# OLED_1_5-inch_Sch.net
KiCad netlist of a schematic drawn in Altium Designer
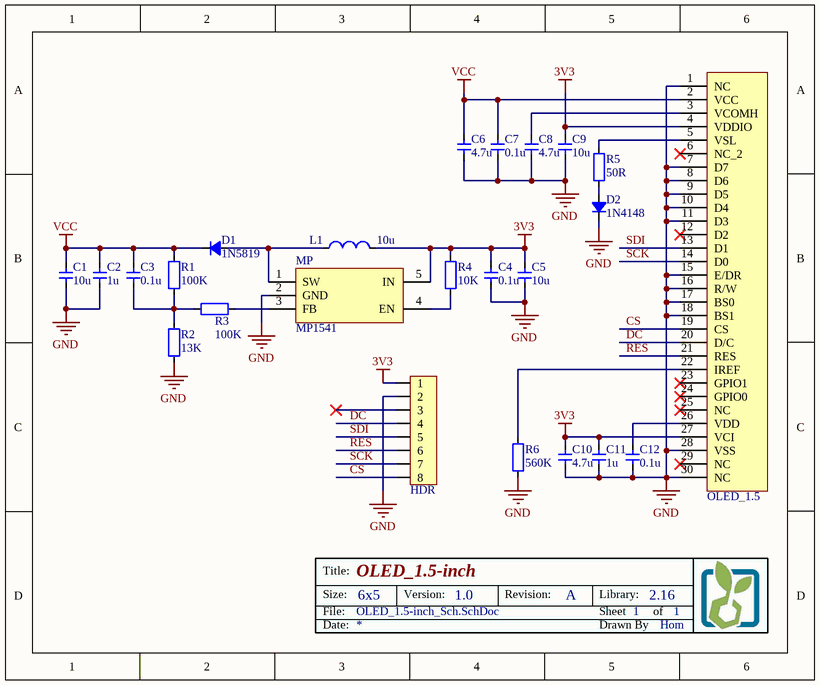
[diagram p0: OLED_1.5-inch_Sch.SchDoc]

(export (version "E")
  (design (tool "Eeschema 10.0.6"))
  (components
    (comp (ref "C1")
      (value "10u")
      (footprint "PCB_PassiveCap:CAP_0805")
      (description "Capacitor")
      (fields (field (name "Comment") "Cap_0805"))
      (libsource (lib "SCH_Passive") (part "Cap_0805"))
    )
    (comp (ref "C2")
      (value "1u")
      (footprint "PCB_PassiveCap:CAP_0805")
      (description "Capacitor")
      (fields (field (name "Comment") "Cap_0805"))
      (libsource (lib "SCH_Passive") (part "Cap_0805"))
    )
    (comp (ref "C3")
      (value "0.1u")
      (footprint "PCB_PassiveCap:CAP_0805")
      (description "Capacitor")
      (fields (field (name "Comment") "Cap_0805"))
      (libsource (lib "SCH_Passive") (part "Cap_0805"))
    )
    (comp (ref "C4")
      (value "0.1u")
      (footprint "PCB_PassiveCap:CAP_0603")
      (description "Capacitor")
      (fields (field (name "Comment") "Cap_0603"))
      (libsource (lib "SCH_Passive") (part "Cap_0603"))
    )
    (comp (ref "C5")
      (value "10u")
      (footprint "PCB_PassiveCap:CAP_0603")
      (description "Capacitor")
      (fields (field (name "Comment") "Cap_0603"))
      (libsource (lib "SCH_Passive") (part "Cap_0603"))
    )
    (comp (ref "C6")
      (value "4.7u")
      (footprint "PCB_PassiveCap:CAP_0805")
      (description "Capacitor")
      (fields (field (name "Comment") "Cap_0805"))
      (libsource (lib "SCH_Passive") (part "Cap_0805"))
    )
    (comp (ref "C7")
      (value "0.1u")
      (footprint "PCB_PassiveCap:CAP_0805")
      (description "Capacitor")
      (fields (field (name "Comment") "Cap_0805"))
      (libsource (lib "SCH_Passive") (part "Cap_0805"))
    )
    (comp (ref "C8")
      (value "4.7u")
      (footprint "PCB_PassiveCap:CAP_0805")
      (description "Capacitor")
      (fields (field (name "Comment") "Cap_0805"))
      (libsource (lib "SCH_Passive") (part "Cap_0805"))
    )
    (comp (ref "C9")
      (value "10u")
      (footprint "PCB_PassiveCap:CAP_0603")
      (description "Capacitor")
      (fields (field (name "Comment") "Cap_0603"))
      (libsource (lib "SCH_Passive") (part "Cap_0603"))
    )
    (comp (ref "C10")
      (value "4.7u")
      (footprint "PCB_PassiveCap:CAP_0603")
      (description "Capacitor")
      (fields (field (name "Comment") "Cap_0603"))
      (libsource (lib "SCH_Passive") (part "Cap_0603"))
    )
    (comp (ref "C11")
      (value "1u")
      (footprint "PCB_PassiveCap:CAP_0603")
      (description "Capacitor")
      (fields (field (name "Comment") "Cap_0603"))
      (libsource (lib "SCH_Passive") (part "Cap_0603"))
    )
    (comp (ref "C12")
      (value "0.1u")
      (footprint "PCB_PassiveCap:CAP_0603")
      (description "Capacitor")
      (fields (field (name "Comment") "Cap_0603"))
      (libsource (lib "SCH_Passive") (part "Cap_0603"))
    )
    (comp (ref "D1")
      (value "1N5819")
      (footprint "PCB_ActiveDIO:SOD-123")
      (description "Diode")
      (libsource (lib "SCH_Active") (part "Diode_SOD123"))
    )
    (comp (ref "D2")
      (value "1N4148")
      (footprint "PCB_ActiveDIO:SOD-323")
      (description "Diode")
      (libsource (lib "SCH_Active") (part "Diode_SOD323"))
    )
    (comp (ref "HDR")
      (value "HDR1x8_2.54")
      (footprint "PCB_ConnectorHDR:HDR1X8_2.54_180")
      (description "Header")
      (libsource (lib "SCH_ConnectorHDR") (part "HDR1x8_2.54"))
    )
    (comp (ref "L1")
      (value "10u")
      (footprint "PCB_PassiveInd:IND_CD32")
      (description "Inductor")
      (fields (field (name "Comment") "Ind_CD32"))
      (libsource (lib "SCH_Passive") (part "Ind_CD32"))
    )
    (comp (ref "MP")
      (value "MP1541")
      (footprint "PCB_IntegratedCircuit:SOT23-5")
      (description "Boost")
      (libsource (lib "SCH_IntegratedCircuit") (part "MP1541"))
    )
    (comp (ref "OLED_1.5")
      (value "OLED_1.5_SSD1351")
      (footprint "PCB_Module:OLED_1.5_128x128_SSD1351")
      (description "OLED")
      (libsource (lib "SCH_Module") (part "OLED_1.5_SSD1351"))
    )
    (comp (ref "R1")
      (value "100K")
      (footprint "PCB_PassiveRes:RES_0603")
      (description "Resistor")
      (fields (field (name "Comment") "Res_0603"))
      (libsource (lib "") (part "Res_0603_2"))
    )
    (comp (ref "R2")
      (value "13K")
      (footprint "PCB_PassiveRes:RES_0603")
      (description "Resistor")
      (fields (field (name "Comment") "Res_0603"))
      (libsource (lib "") (part "Res_0603_2"))
    )
    (comp (ref "R3")
      (value "100K")
      (footprint "PCB_PassiveRes:RES_0603")
      (description "Resistor")
      (fields (field (name "Comment") "Res_0603"))
      (libsource (lib "") (part "Res_0603_1"))
    )
    (comp (ref "R4")
      (value "10K")
      (footprint "PCB_PassiveRes:RES_0603")
      (description "Resistor")
      (fields (field (name "Comment") "Res_0603"))
      (libsource (lib "") (part "Res_0603_2"))
    )
    (comp (ref "R5")
      (value "50R")
      (footprint "PCB_PassiveRes:RES_0603")
      (description "Resistor")
      (fields (field (name "Comment") "Res_0603"))
      (libsource (lib "SCH_Passive") (part "Res_0603"))
    )
    (comp (ref "R6")
      (value "560K")
      (footprint "PCB_PassiveRes:RES_0603")
      (description "Resistor")
      (fields (field (name "Comment") "Res_0603"))
      (libsource (lib "SCH_Passive") (part "Res_0603"))
    )
  )
  (nets
    (net (code "1") (name "/CS") (class "Default")
      (node (ref "HDR") (pin "8") (pinfunction "8_8") (pintype "passive"))
      (node (ref "OLED_1.5") (pin "19") (pinfunction "CS_19") (pintype "passive"))
    )
    (net (code "2") (name "/DC") (class "Default")
      (node (ref "HDR") (pin "4") (pinfunction "4_4") (pintype "passive"))
      (node (ref "OLED_1.5") (pin "20") (pinfunction "D/C_20") (pintype "passive"))
    )
    (net (code "3") (name "/RES") (class "Default")
      (node (ref "HDR") (pin "6") (pinfunction "6_6") (pintype "passive"))
      (node (ref "OLED_1.5") (pin "21") (pinfunction "RES_21") (pintype "passive"))
    )
    (net (code "4") (name "/SCK") (class "Default")
      (node (ref "HDR") (pin "7") (pinfunction "7_7") (pintype "passive"))
      (node (ref "OLED_1.5") (pin "14") (pinfunction "D0_14") (pintype "passive"))
    )
    (net (code "5") (name "/SDI") (class "Default")
      (node (ref "HDR") (pin "5") (pinfunction "5_5") (pintype "passive"))
      (node (ref "OLED_1.5") (pin "13") (pinfunction "D1_13") (pintype "passive"))
    )
    (net (code "6") (name "3V3") (class "Default")
      (node (ref "C10") (pin "2") (pinfunction "2_2") (pintype "passive"))
      (node (ref "C11") (pin "2") (pinfunction "2_2") (pintype "passive"))
      (node (ref "C4") (pin "2") (pinfunction "2_2") (pintype "passive"))
      (node (ref "C5") (pin "2") (pinfunction "2_2") (pintype "passive"))
      (node (ref "C9") (pin "2") (pinfunction "2_2") (pintype "passive"))
      (node (ref "HDR") (pin "1") (pinfunction "1_1") (pintype "passive"))
      (node (ref "L1") (pin "2") (pinfunction "2_2") (pintype "passive"))
      (node (ref "MP") (pin "5") (pinfunction "IN_5") (pintype "passive"))
      (node (ref "OLED_1.5") (pin "27") (pinfunction "VCI_27") (pintype "passive"))
      (node (ref "OLED_1.5") (pin "4") (pinfunction "VDDIO_4") (pintype "passive"))
      (node (ref "R4") (pin "2") (pinfunction "2_2") (pintype "passive"))
    )
    (net (code "7") (name "GND") (class "Default")
      (node (ref "C1") (pin "1") (pinfunction "1_1") (pintype "passive"))
      (node (ref "C10") (pin "1") (pinfunction "1_1") (pintype "passive"))
      (node (ref "C11") (pin "1") (pinfunction "1_1") (pintype "passive"))
      (node (ref "C12") (pin "1") (pinfunction "1_1") (pintype "passive"))
      (node (ref "C2") (pin "1") (pinfunction "1_1") (pintype "passive"))
      (node (ref "C4") (pin "1") (pinfunction "1_1") (pintype "passive"))
      (node (ref "C5") (pin "1") (pinfunction "1_1") (pintype "passive"))
      (node (ref "C6") (pin "1") (pinfunction "1_1") (pintype "passive"))
      (node (ref "C7") (pin "1") (pinfunction "1_1") (pintype "passive"))
      (node (ref "C8") (pin "1") (pinfunction "1_1") (pintype "passive"))
      (node (ref "C9") (pin "1") (pinfunction "1_1") (pintype "passive"))
      (node (ref "D2") (pin "2") (pinfunction "K_2") (pintype "passive"))
      (node (ref "HDR") (pin "2") (pinfunction "2_2") (pintype "passive"))
      (node (ref "MP") (pin "2") (pinfunction "GND_2") (pintype "passive"))
      (node (ref "OLED_1.5") (pin "1") (pinfunction "NC_1") (pintype "passive"))
      (node (ref "OLED_1.5") (pin "10") (pinfunction "D4_10") (pintype "passive"))
      (node (ref "OLED_1.5") (pin "11") (pinfunction "D3_11") (pintype "passive"))
      (node (ref "OLED_1.5") (pin "15") (pinfunction "E/DR_15") (pintype "passive"))
      (node (ref "OLED_1.5") (pin "16") (pinfunction "R/W_16") (pintype "passive"))
      (node (ref "OLED_1.5") (pin "17") (pinfunction "BS0_17") (pintype "passive"))
      (node (ref "OLED_1.5") (pin "18") (pinfunction "BS1_18") (pintype "passive"))
      (node (ref "OLED_1.5") (pin "28") (pinfunction "VSS_28") (pintype "passive"))
      (node (ref "OLED_1.5") (pin "30") (pinfunction "NC_30") (pintype "passive"))
      (node (ref "OLED_1.5") (pin "7") (pinfunction "D7_7") (pintype "passive"))
      (node (ref "OLED_1.5") (pin "8") (pinfunction "D6_8") (pintype "passive"))
      (node (ref "OLED_1.5") (pin "9") (pinfunction "D5_9") (pintype "passive"))
      (node (ref "R2") (pin "1") (pinfunction "1_1") (pintype "passive"))
      (node (ref "R6") (pin "2") (pinfunction "2_2") (pintype "passive"))
    )
    (net (code "8") (name "Net-(C3-Pad1)") (class "Default")
      (node (ref "C3") (pin "1") (pinfunction "1_1") (pintype "passive"))
      (node (ref "R1") (pin "1") (pinfunction "1_1") (pintype "passive"))
      (node (ref "R2") (pin "2") (pinfunction "2_2") (pintype "passive"))
      (node (ref "R3") (pin "2") (pinfunction "2_2") (pintype "passive"))
    )
    (net (code "9") (name "Net-(D1-A)") (class "Default")
      (node (ref "D1") (pin "1") (pinfunction "A_1") (pintype "passive"))
      (node (ref "L1") (pin "1") (pinfunction "1_1") (pintype "passive"))
      (node (ref "MP") (pin "1") (pinfunction "SW_1") (pintype "passive"))
    )
    (net (code "10") (name "Net-(D2-A)") (class "Default")
      (node (ref "D2") (pin "1") (pinfunction "A_1") (pintype "passive"))
      (node (ref "R5") (pin "2") (pinfunction "2_2") (pintype "passive"))
    )
    (net (code "11") (name "Net-(MP-EN)") (class "Default")
      (node (ref "MP") (pin "4") (pinfunction "EN_4") (pintype "passive"))
      (node (ref "R4") (pin "1") (pinfunction "1_1") (pintype "passive"))
    )
    (net (code "12") (name "Net-(MP-FB)") (class "Default")
      (node (ref "MP") (pin "3") (pinfunction "FB_3") (pintype "passive"))
      (node (ref "R3") (pin "1") (pinfunction "1_1") (pintype "passive"))
    )
    (net (code "13") (name "Net-(OLED_1.5-IREF)") (class "Default")
      (node (ref "OLED_1.5") (pin "22") (pinfunction "IREF_22") (pintype "passive"))
      (node (ref "R6") (pin "1") (pinfunction "1_1") (pintype "passive"))
    )
    (net (code "14") (name "Net-(OLED_1.5-VCOMH)") (class "Default")
      (node (ref "C8") (pin "2") (pinfunction "2_2") (pintype "passive"))
      (node (ref "OLED_1.5") (pin "3") (pinfunction "VCOMH_3") (pintype "passive"))
    )
    (net (code "15") (name "Net-(OLED_1.5-VDD)") (class "Default")
      (node (ref "C12") (pin "2") (pinfunction "2_2") (pintype "passive"))
      (node (ref "OLED_1.5") (pin "26") (pinfunction "VDD_26") (pintype "passive"))
    )
    (net (code "16") (name "Net-(OLED_1.5-VSL)") (class "Default")
      (node (ref "OLED_1.5") (pin "5") (pinfunction "VSL_5") (pintype "passive"))
      (node (ref "R5") (pin "1") (pinfunction "1_1") (pintype "passive"))
    )
    (net (code "17") (name "VCC") (class "Default")
      (node (ref "C1") (pin "2") (pinfunction "2_2") (pintype "passive"))
      (node (ref "C2") (pin "2") (pinfunction "2_2") (pintype "passive"))
      (node (ref "C3") (pin "2") (pinfunction "2_2") (pintype "passive"))
      (node (ref "C6") (pin "2") (pinfunction "2_2") (pintype "passive"))
      (node (ref "C7") (pin "2") (pinfunction "2_2") (pintype "passive"))
      (node (ref "D1") (pin "2") (pinfunction "K_2") (pintype "passive"))
      (node (ref "OLED_1.5") (pin "2") (pinfunction "VCC_2") (pintype "passive"))
      (node (ref "R1") (pin "2") (pinfunction "2_2") (pintype "passive"))
    )
    (net (code "18") (name "unconnected-(HDR-Pad3)") (class "Default")
      (node (ref "HDR") (pin "3") (pinfunction "3_3") (pintype "passive+no_connect"))
    )
    (net (code "19") (name "unconnected-(OLED_1.5-D2-Pad12)") (class "Default")
      (node (ref "OLED_1.5") (pin "12") (pinfunction "D2_12") (pintype "passive+no_connect"))
    )
    (net (code "20") (name "unconnected-(OLED_1.5-GPIO0-Pad24)") (class "Default")
      (node (ref "OLED_1.5") (pin "24") (pinfunction "GPIO0_24") (pintype "passive+no_connect"))
    )
    (net (code "21") (name "unconnected-(OLED_1.5-GPIO1-Pad23)") (class "Default")
      (node (ref "OLED_1.5") (pin "23") (pinfunction "GPIO1_23") (pintype "passive+no_connect"))
    )
    (net (code "22") (name "unconnected-(OLED_1.5-NC-Pad25)") (class "Default")
      (node (ref "OLED_1.5") (pin "25") (pinfunction "NC_25") (pintype "passive+no_connect"))
    )
    (net (code "23") (name "unconnected-(OLED_1.5-NC-Pad29)") (class "Default")
      (node (ref "OLED_1.5") (pin "29") (pinfunction "NC_29") (pintype "passive+no_connect"))
    )
    (net (code "24") (name "unconnected-(OLED_1.5-NC_2-Pad6)") (class "Default")
      (node (ref "OLED_1.5") (pin "6") (pinfunction "NC_2_6") (pintype "passive+no_connect"))
    )
  )
)
